# TopLevel.net
KiCad netlist of a schematic drawn in Altium Designer
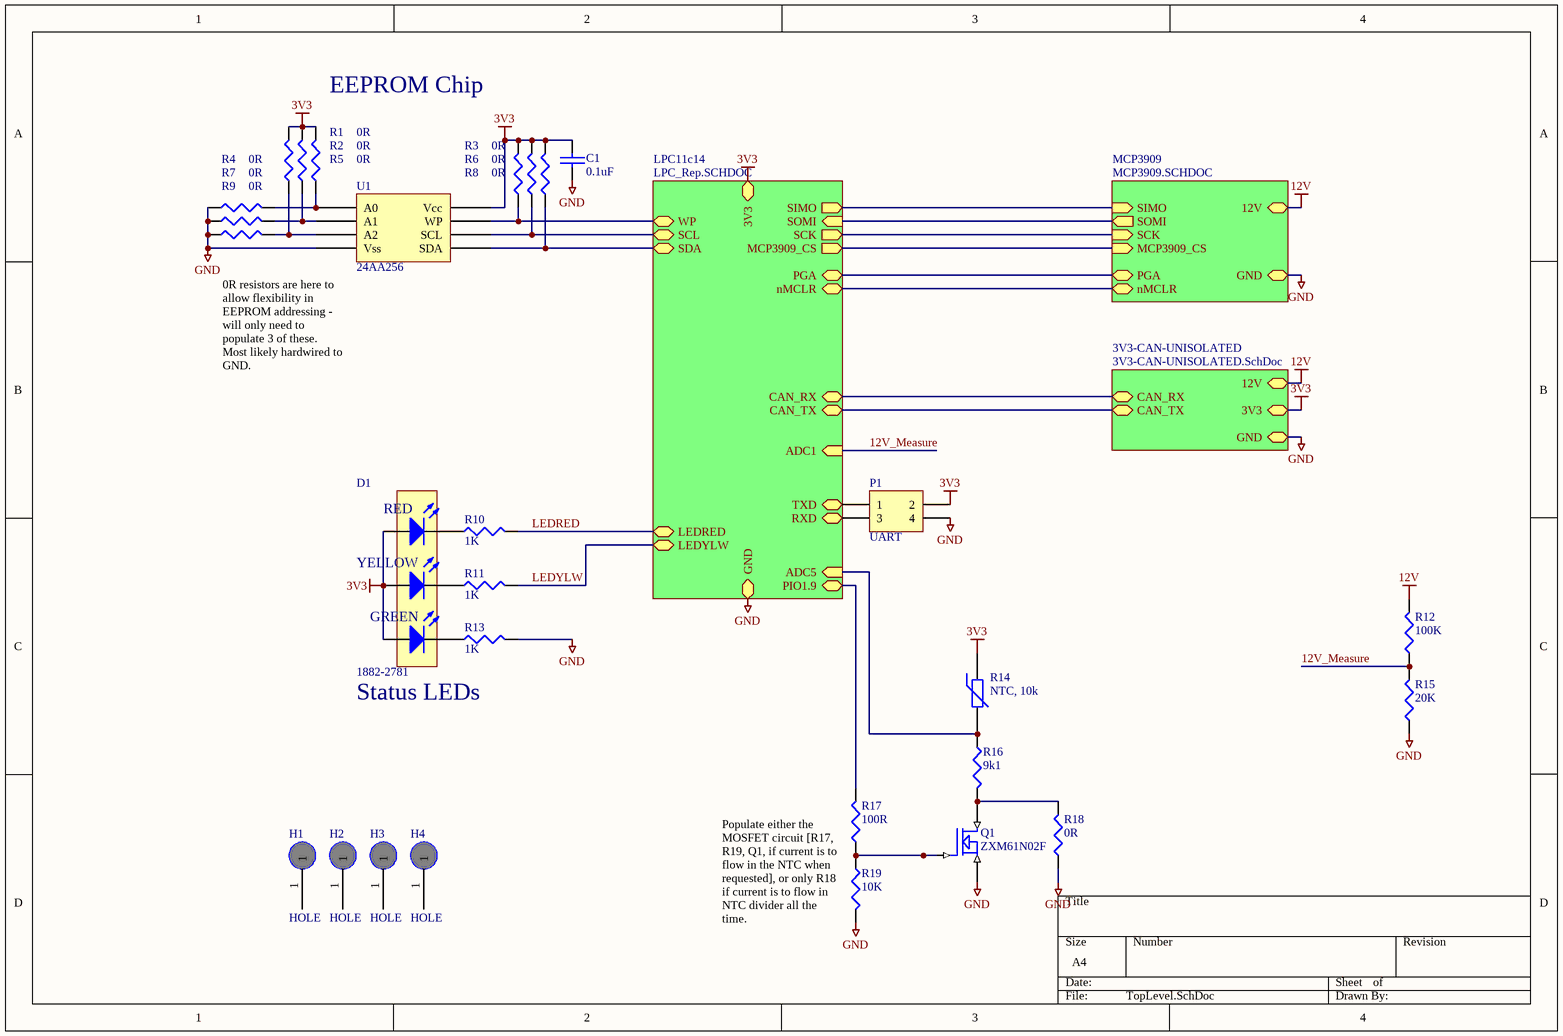
[diagram p0: TopLevel.SchDoc]

(export (version "E")
  (design (tool "Eeschema 10.0.6"))
  (components
    (comp (ref "C1")
      (value "0.1uF")
      (footprint "0805")
      (description "Capacitor")
      (libsource (lib "*") (part "CAP"))
    )
    (comp (ref "D1")
      (value "1882-2781")
      (footprint "LED_TRILEVEL")
      (description "Three level LED")
      (libsource (lib "RCLDQ") (part "LED-TRILEVEL"))
    )
    (comp (ref "H1")
      (value "HOLE")
      (footprint "M2.5")
      (description "Hole")
      (libsource (lib "Miscellaneous") (part "HOLE"))
    )
    (comp (ref "H2")
      (value "HOLE")
      (footprint "M2.5")
      (description "Hole")
      (libsource (lib "Miscellaneous") (part "HOLE"))
    )
    (comp (ref "H3")
      (value "HOLE")
      (footprint "M2.5")
      (description "Hole")
      (libsource (lib "Miscellaneous") (part "HOLE"))
    )
    (comp (ref "H4")
      (value "HOLE")
      (footprint "M2.5")
      (description "Hole")
      (libsource (lib "Miscellaneous") (part "HOLE"))
    )
    (comp (ref "P1")
      (value "UART")
      (footprint "HDR2X2")
      (description "Header, 2-Pin, Dual row")
      (fields (field (name "PUBLISHER") "Altium Limited"))
      (libsource (lib "Miscellaneous Connectors") (part "Header 2X2"))
    )
    (comp (ref "Q1")
      (value "ZXM61N02F")
      (footprint "SOT23-3")
      (description "1.7A, 20V N-Channel Enhancement mode FET")
      (libsource (lib "RCLDQ") (part "ZXM61N02F"))
    )
    (comp (ref "R1")
      (value "0R")
      (footprint "0603")
      (description "Resistor")
      (libsource (lib "SunswiftLib20030312RR") (part "RES1"))
    )
    (comp (ref "R2")
      (value "0R")
      (footprint "0603")
      (description "Resistor")
      (libsource (lib "SunswiftLib20030312RR") (part "RES1"))
    )
    (comp (ref "R3")
      (value "0R")
      (footprint "0603")
      (description "Resistor")
      (libsource (lib "SunswiftLib20030312RR") (part "RES1"))
    )
    (comp (ref "R4")
      (value "0R")
      (footprint "0603")
      (description "Resistor")
      (libsource (lib "SunswiftLib20030312RR") (part "RES1"))
    )
    (comp (ref "R5")
      (value "0R")
      (footprint "0603")
      (description "Resistor")
      (libsource (lib "SunswiftLib20030312RR") (part "RES1"))
    )
    (comp (ref "R6")
      (value "0R")
      (footprint "0603")
      (description "Resistor")
      (libsource (lib "SunswiftLib20030312RR") (part "RES1"))
    )
    (comp (ref "R7")
      (value "0R")
      (footprint "0603")
      (description "Resistor")
      (libsource (lib "SunswiftLib20030312RR") (part "RES1"))
    )
    (comp (ref "R8")
      (value "0R")
      (footprint "0603")
      (description "Resistor")
      (libsource (lib "SunswiftLib20030312RR") (part "RES1"))
    )
    (comp (ref "R9")
      (value "0R")
      (footprint "0603")
      (description "Resistor")
      (libsource (lib "SunswiftLib20030312RR") (part "RES1"))
    )
    (comp (ref "R10")
      (value "1K")
      (footprint "0603")
      (description "Resistor")
      (libsource (lib "RCLDQ") (part "RES1"))
    )
    (comp (ref "R11")
      (value "1K")
      (footprint "0603")
      (description "Resistor")
      (libsource (lib "RCLDQ") (part "RES1"))
    )
    (comp (ref "R12")
      (value "100K")
      (footprint "1206")
      (description "Resistor")
      (libsource (lib "2009_BatteryMaster") (part "RES1"))
    )
    (comp (ref "R13")
      (value "1K")
      (footprint "0603")
      (description "Resistor")
      (libsource (lib "RCLDQ") (part "RES1"))
    )
    (comp (ref "R14")
      (value "NTC, 10k")
      (footprint "NTC_EPCOS")
      (description "Varistor (Voltage-Sensitive Resistor)")
      (libsource (lib "Miscellaneous Devices") (part "Res Varistor"))
    )
    (comp (ref "R15")
      (value "20K")
      (footprint "1206")
      (description "Resistor")
      (libsource (lib "2009_BatteryMaster") (part "RES1"))
    )
    (comp (ref "R16")
      (value "9k1")
      (footprint "0603")
      (description "Resistor")
      (libsource (lib "SUNSWIFTLIB") (part "RES1"))
    )
    (comp (ref "R17")
      (value "100R")
      (footprint "0603")
      (description "Resistor")
      (libsource (lib "SUNSWIFTLIB") (part "RES1"))
    )
    (comp (ref "R18")
      (value "0R")
      (footprint "0603")
      (description "Resistor")
      (libsource (lib "SUNSWIFTLIB") (part "RES1"))
    )
    (comp (ref "R19")
      (value "10K")
      (footprint "0603")
      (description "Resistor")
      (libsource (lib "SUNSWIFTLIB") (part "RES1"))
    )
    (comp (ref "U1") (value "24AA256") (footprint "DIP8") (libsource (lib "Miscellaneous") (part "24AA256")))
  )
  (nets
    (net (code "1") (name "/12V_Measure") (class "Default")
      (node (ref "R12") (pin "1") (pinfunction "1_1") (pintype "passive"))
      (node (ref "R15") (pin "2") (pinfunction "2_2") (pintype "passive"))
    )
    (net (code "2") (name "/ADC5") (class "Default")
      (node (ref "R14") (pin "2") (pinfunction "2_2") (pintype "passive"))
      (node (ref "R16") (pin "1") (pinfunction "1_1") (pintype "passive"))
    )
    (net (code "5") (name "/LEDRED") (class "Default")
      (node (ref "R10") (pin "2") (pinfunction "2_2") (pintype "passive"))
    )
    (net (code "6") (name "/LEDYLW") (class "Default")
      (node (ref "R11") (pin "2") (pinfunction "2_2") (pintype "passive"))
    )
    (net (code "9") (name "/PIO1.9") (class "Default")
      (node (ref "R17") (pin "2") (pinfunction "2_2") (pintype "passive"))
    )
    (net (code "10") (name "/RXD") (class "Default")
      (node (ref "P1") (pin "3") (pinfunction "3_3") (pintype "passive"))
    )
    (net (code "12") (name "/SCL") (class "Default")
      (node (ref "R6") (pin "1") (pinfunction "1_1") (pintype "passive"))
      (node (ref "U1") (pin "6") (pinfunction "SCL_6") (pintype "passive"))
    )
    (net (code "13") (name "/SDA") (class "Default")
      (node (ref "R3") (pin "1") (pinfunction "1_1") (pintype "passive"))
      (node (ref "U1") (pin "5") (pinfunction "SDA_5") (pintype "passive"))
    )
    (net (code "16") (name "/TXD") (class "Default")
      (node (ref "P1") (pin "1") (pinfunction "1_1") (pintype "passive"))
    )
    (net (code "17") (name "/WP") (class "Default")
      (node (ref "R8") (pin "1") (pinfunction "1_1") (pintype "passive"))
      (node (ref "U1") (pin "7") (pinfunction "WP_7") (pintype "passive"))
    )
    (net (code "19") (name "3V3") (class "Default")
      (node (ref "C1") (pin "1") (pinfunction "1_1") (pintype "passive"))
      (node (ref "D1") (pin "4") (pinfunction "A_4") (pintype "passive"))
      (node (ref "D1") (pin "5") (pinfunction "A_5") (pintype "passive"))
      (node (ref "D1") (pin "6") (pinfunction "A_6") (pintype "passive"))
      (node (ref "P1") (pin "2") (pinfunction "2_2") (pintype "passive"))
      (node (ref "R1") (pin "2") (pinfunction "2_2") (pintype "passive"))
      (node (ref "R14") (pin "1") (pinfunction "1_1") (pintype "passive"))
      (node (ref "R2") (pin "2") (pinfunction "2_2") (pintype "passive"))
      (node (ref "R3") (pin "2") (pinfunction "2_2") (pintype "passive"))
      (node (ref "R5") (pin "2") (pinfunction "2_2") (pintype "passive"))
      (node (ref "R6") (pin "2") (pinfunction "2_2") (pintype "passive"))
      (node (ref "R8") (pin "2") (pinfunction "2_2") (pintype "passive"))
      (node (ref "U1") (pin "8") (pinfunction "Vcc_8") (pintype "passive"))
    )
    (net (code "20") (name "12V") (class "Default")
      (node (ref "R12") (pin "2") (pinfunction "2_2") (pintype "passive"))
    )
    (net (code "21") (name "GND") (class "Default")
      (node (ref "C1") (pin "2") (pinfunction "2_2") (pintype "passive"))
      (node (ref "P1") (pin "4") (pinfunction "4_4") (pintype "passive"))
      (node (ref "Q1") (pin "2") (pinfunction "S_2") (pintype "input"))
      (node (ref "R13") (pin "2") (pinfunction "2_2") (pintype "passive"))
      (node (ref "R15") (pin "1") (pinfunction "1_1") (pintype "passive"))
      (node (ref "R18") (pin "1") (pinfunction "1_1") (pintype "passive"))
      (node (ref "R19") (pin "2") (pinfunction "2_2") (pintype "passive"))
      (node (ref "R4") (pin "1") (pinfunction "1_1") (pintype "passive"))
      (node (ref "R7") (pin "1") (pinfunction "1_1") (pintype "passive"))
      (node (ref "R9") (pin "1") (pinfunction "1_1") (pintype "passive"))
      (node (ref "U1") (pin "4") (pinfunction "Vss_4") (pintype "passive"))
    )
    (net (code "22") (name "Net-(D1-K-Pad1)") (class "Default")
      (node (ref "D1") (pin "1") (pinfunction "K_1") (pintype "passive"))
      (node (ref "R13") (pin "1") (pinfunction "1_1") (pintype "passive"))
    )
    (net (code "23") (name "Net-(D1-K-Pad2)") (class "Default")
      (node (ref "D1") (pin "2") (pinfunction "K_2") (pintype "passive"))
      (node (ref "R11") (pin "1") (pinfunction "1_1") (pintype "passive"))
    )
    (net (code "24") (name "Net-(D1-K-Pad3)") (class "Default")
      (node (ref "D1") (pin "3") (pinfunction "K_3") (pintype "passive"))
      (node (ref "R10") (pin "1") (pinfunction "1_1") (pintype "passive"))
    )
    (net (code "25") (name "Net-(Q1-D)") (class "Default")
      (node (ref "Q1") (pin "3") (pinfunction "D_3") (pintype "input"))
      (node (ref "R16") (pin "2") (pinfunction "2_2") (pintype "passive"))
      (node (ref "R18") (pin "2") (pinfunction "2_2") (pintype "passive"))
    )
    (net (code "26") (name "Net-(Q1-G)") (class "Default")
      (node (ref "Q1") (pin "1") (pinfunction "G_1") (pintype "input"))
      (node (ref "R17") (pin "1") (pinfunction "1_1") (pintype "passive"))
      (node (ref "R19") (pin "1") (pinfunction "1_1") (pintype "passive"))
    )
    (net (code "27") (name "Net-(U1-A0)") (class "Default")
      (node (ref "R1") (pin "1") (pinfunction "1_1") (pintype "passive"))
      (node (ref "R4") (pin "2") (pinfunction "2_2") (pintype "passive"))
      (node (ref "U1") (pin "1") (pinfunction "A0_1") (pintype "passive"))
    )
    (net (code "28") (name "Net-(U1-A1)") (class "Default")
      (node (ref "R2") (pin "1") (pinfunction "1_1") (pintype "passive"))
      (node (ref "R7") (pin "2") (pinfunction "2_2") (pintype "passive"))
      (node (ref "U1") (pin "2") (pinfunction "A1_2") (pintype "passive"))
    )
    (net (code "29") (name "Net-(U1-A2)") (class "Default")
      (node (ref "R5") (pin "1") (pinfunction "1_1") (pintype "passive"))
      (node (ref "R9") (pin "2") (pinfunction "2_2") (pintype "passive"))
      (node (ref "U1") (pin "3") (pinfunction "A2_3") (pintype "passive"))
    )
    (net (code "30") (name "unconnected-(H1-Pad1)") (class "Default")
      (node (ref "H1") (pin "1") (pinfunction "1_1") (pintype "passive"))
    )
    (net (code "31") (name "unconnected-(H2-Pad1)") (class "Default")
      (node (ref "H2") (pin "1") (pinfunction "1_1") (pintype "passive"))
    )
    (net (code "32") (name "unconnected-(H3-Pad1)") (class "Default")
      (node (ref "H3") (pin "1") (pinfunction "1_1") (pintype "passive"))
    )
    (net (code "33") (name "unconnected-(H4-Pad1)") (class "Default")
      (node (ref "H4") (pin "1") (pinfunction "1_1") (pintype "passive"))
    )
  )
)
